# Connectors.net
KiCad netlist of a schematic drawn in Altium Designer
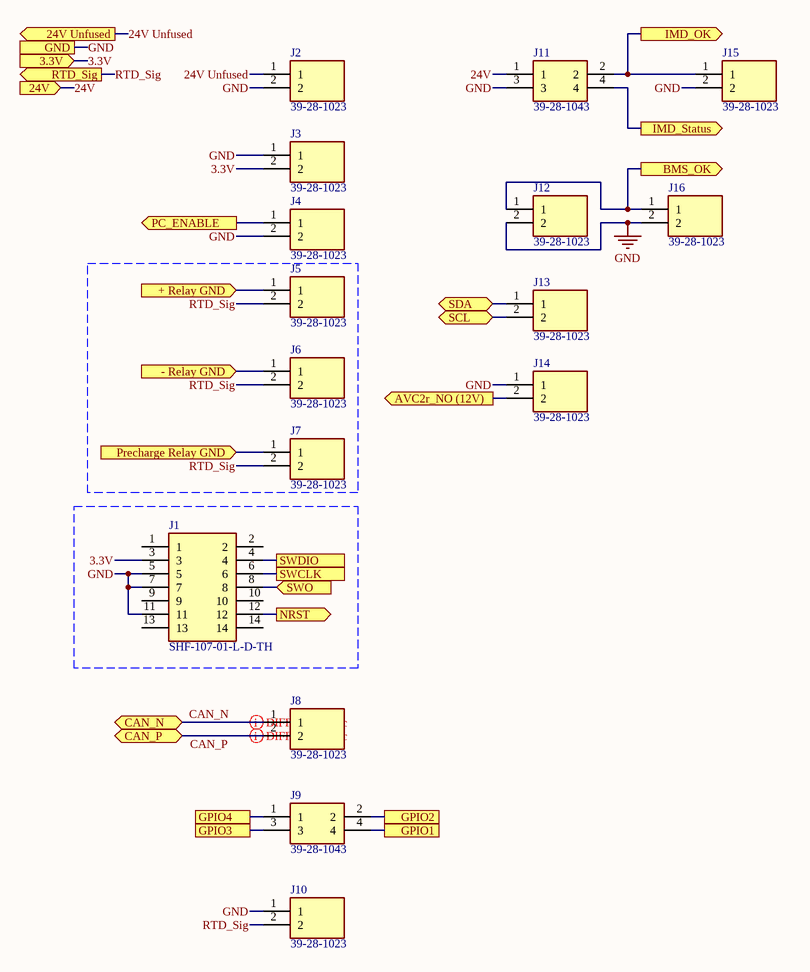
[diagram p0: Connectors.SchDoc]

(export (version "E")
  (design (tool "Eeschema 10.0.6"))
  (components
    (comp (ref "J1")
      (value "SHF-107-01-L-D-TH")
      (footprint "SamacSys:SHF10701LDTH")
      (description "Connector")
      (fields (field (name "MOUSER PART NUMBER") "200-SHF10701LDTH"))
      (libsource (lib "SamacSys") (part "SHF-107-01-L-D-TH"))
    )
    (comp (ref "J2")
      (value "39-28-1023")
      (footprint "SamacSys:39-28-1023")
      (description "Connector")
      (fields (field (name "MOUSER PART NUMBER") "538-39-28-1023"))
      (libsource (lib "SamacSys") (part "39-28-1023"))
    )
    (comp (ref "J3")
      (value "39-28-1023")
      (footprint "SamacSys:39-28-1023")
      (description "Connector")
      (fields (field (name "MOUSER PART NUMBER") "538-39-28-1023"))
      (libsource (lib "SamacSys") (part "39-28-1023"))
    )
    (comp (ref "J4")
      (value "39-28-1023")
      (footprint "SamacSys:39-28-1023")
      (description "Connector")
      (fields (field (name "MOUSER PART NUMBER") "538-39-28-1023"))
      (libsource (lib "SamacSys") (part "39-28-1023"))
    )
    (comp (ref "J5")
      (value "39-28-1023")
      (footprint "SamacSys:39-28-1023")
      (description "Connector")
      (fields (field (name "MOUSER PART NUMBER") "538-39-28-1023"))
      (libsource (lib "SamacSys") (part "39-28-1023"))
    )
    (comp (ref "J6")
      (value "39-28-1023")
      (footprint "SamacSys:39-28-1023")
      (description "Connector")
      (fields (field (name "MOUSER PART NUMBER") "538-39-28-1023"))
      (libsource (lib "SamacSys") (part "39-28-1023"))
    )
    (comp (ref "J7")
      (value "39-28-1023")
      (footprint "SamacSys:39-28-1023")
      (description "Connector")
      (fields (field (name "MOUSER PART NUMBER") "538-39-28-1023"))
      (libsource (lib "SamacSys") (part "39-28-1023"))
    )
    (comp (ref "J8")
      (value "39-28-1023")
      (footprint "SamacSys:39-28-1023")
      (description "Connector")
      (fields (field (name "MOUSER PART NUMBER") "538-39-28-1023"))
      (libsource (lib "SamacSys") (part "39-28-1023"))
    )
    (comp (ref "J9")
      (value "39-28-1043")
      (footprint "SamacSys:39-28-1043")
      (description "Connector")
      (fields (field (name "MOUSER PART NUMBER") "538-39-28-1043"))
      (libsource (lib "*") (part "39-28-1043"))
    )
    (comp (ref "J10")
      (value "39-28-1023")
      (footprint "SamacSys:39-28-1023")
      (description "Connector")
      (fields (field (name "MOUSER PART NUMBER") "538-39-28-1023"))
      (libsource (lib "SamacSys") (part "39-28-1023"))
    )
    (comp (ref "J11")
      (value "39-28-1043")
      (footprint "SamacSys:39-28-1043")
      (description "Connector")
      (fields (field (name "MOUSER PART NUMBER") "538-39-28-1043"))
      (libsource (lib "*") (part "39-28-1043"))
    )
    (comp (ref "J12")
      (value "39-28-1023")
      (footprint "SamacSys:39-28-1023")
      (description "Connector")
      (fields (field (name "MOUSER PART NUMBER") "538-39-28-1023"))
      (libsource (lib "SamacSys") (part "39-28-1023"))
    )
    (comp (ref "J13")
      (value "39-28-1023")
      (footprint "SamacSys:39-28-1023")
      (description "Connector")
      (fields (field (name "MOUSER PART NUMBER") "538-39-28-1023"))
      (libsource (lib "SamacSys") (part "39-28-1023"))
    )
    (comp (ref "J14")
      (value "39-28-1023")
      (footprint "SamacSys:39-28-1023")
      (description "Connector")
      (fields (field (name "MOUSER PART NUMBER") "538-39-28-1023"))
      (libsource (lib "SamacSys") (part "39-28-1023"))
    )
    (comp (ref "J15")
      (value "39-28-1023")
      (footprint "SamacSys:39-28-1023")
      (description "Connector")
      (fields (field (name "MOUSER PART NUMBER") "538-39-28-1023"))
      (libsource (lib "SamacSys") (part "39-28-1023"))
    )
    (comp (ref "J16")
      (value "39-28-1023")
      (footprint "SamacSys:39-28-1023")
      (description "Connector")
      (fields (field (name "MOUSER PART NUMBER") "538-39-28-1023"))
      (libsource (lib "SamacSys") (part "39-28-1023"))
    )
  )
  (nets
    (net (code "1") (name "/+ Relay GND") (class "Default")
      (node (ref "J5") (pin "1") (pinfunction "1_1") (pintype "passive"))
    )
    (net (code "2") (name "/- Relay GND") (class "Default")
      (node (ref "J6") (pin "1") (pinfunction "1_1") (pintype "passive"))
    )
    (net (code "3") (name "/3.3V") (class "Default")
      (node (ref "J1") (pin "3") (pinfunction "3_3") (pintype "passive"))
      (node (ref "J3") (pin "2") (pinfunction "2_2") (pintype "passive"))
    )
    (net (code "4") (name "/24V") (class "Default")
      (node (ref "J11") (pin "1") (pinfunction "1_1") (pintype "passive"))
    )
    (net (code "5") (name "/24V Unfused") (class "Default")
      (node (ref "J2") (pin "1") (pinfunction "1_1") (pintype "passive"))
    )
    (net (code "6") (name "/AVC2r_NO (12V)") (class "Default")
      (node (ref "J14") (pin "2") (pinfunction "2_2") (pintype "passive"))
    )
    (net (code "7") (name "/BMS_OK") (class "Default")
      (node (ref "J12") (pin "1") (pinfunction "1_1") (pintype "passive"))
      (node (ref "J16") (pin "1") (pinfunction "1_1") (pintype "passive"))
    )
    (net (code "8") (name "/CAN_N") (class "Default")
      (node (ref "J8") (pin "1") (pinfunction "1_1") (pintype "passive"))
    )
    (net (code "9") (name "/CAN_P") (class "Default")
      (node (ref "J8") (pin "2") (pinfunction "2_2") (pintype "passive"))
    )
    (net (code "10") (name "/GPIO1") (class "Default")
      (node (ref "J9") (pin "4") (pinfunction "4_4") (pintype "passive"))
    )
    (net (code "11") (name "/GPIO2") (class "Default")
      (node (ref "J9") (pin "2") (pinfunction "2_2") (pintype "passive"))
    )
    (net (code "12") (name "/GPIO3") (class "Default")
      (node (ref "J9") (pin "3") (pinfunction "3_3") (pintype "passive"))
    )
    (net (code "13") (name "/GPIO4") (class "Default")
      (node (ref "J9") (pin "1") (pinfunction "1_1") (pintype "passive"))
    )
    (net (code "14") (name "/IMD_OK") (class "Default")
      (node (ref "J11") (pin "2") (pinfunction "2_2") (pintype "passive"))
      (node (ref "J15") (pin "1") (pinfunction "1_1") (pintype "passive"))
    )
    (net (code "15") (name "/IMD_Status") (class "Default")
      (node (ref "J11") (pin "4") (pinfunction "4_4") (pintype "passive"))
    )
    (net (code "16") (name "/NRST") (class "Default")
      (node (ref "J1") (pin "12") (pinfunction "12_12") (pintype "passive"))
    )
    (net (code "17") (name "/PC_ENABLE") (class "Default")
      (node (ref "J4") (pin "1") (pinfunction "1_1") (pintype "passive"))
    )
    (net (code "18") (name "/Precharge Relay GND") (class "Default")
      (node (ref "J7") (pin "1") (pinfunction "1_1") (pintype "passive"))
    )
    (net (code "19") (name "/RTD_Sig") (class "Default")
      (node (ref "J10") (pin "2") (pinfunction "2_2") (pintype "passive"))
      (node (ref "J5") (pin "2") (pinfunction "2_2") (pintype "passive"))
      (node (ref "J6") (pin "2") (pinfunction "2_2") (pintype "passive"))
      (node (ref "J7") (pin "2") (pinfunction "2_2") (pintype "passive"))
    )
    (net (code "20") (name "/SCL") (class "Default")
      (node (ref "J13") (pin "2") (pinfunction "2_2") (pintype "passive"))
    )
    (net (code "21") (name "/SDA") (class "Default")
      (node (ref "J13") (pin "1") (pinfunction "1_1") (pintype "passive"))
    )
    (net (code "22") (name "/SWCLK") (class "Default")
      (node (ref "J1") (pin "6") (pinfunction "6_6") (pintype "passive"))
    )
    (net (code "23") (name "/SWDIO") (class "Default")
      (node (ref "J1") (pin "4") (pinfunction "4_4") (pintype "passive"))
    )
    (net (code "24") (name "/SWO") (class "Default")
      (node (ref "J1") (pin "8") (pinfunction "8_8") (pintype "passive"))
    )
    (net (code "25") (name "GND") (class "Default")
      (node (ref "J1") (pin "11") (pinfunction "11_11") (pintype "passive"))
      (node (ref "J1") (pin "5") (pinfunction "5_5") (pintype "passive"))
      (node (ref "J1") (pin "7") (pinfunction "7_7") (pintype "passive"))
      (node (ref "J10") (pin "1") (pinfunction "1_1") (pintype "passive"))
      (node (ref "J11") (pin "3") (pinfunction "3_3") (pintype "passive"))
      (node (ref "J12") (pin "2") (pinfunction "2_2") (pintype "passive"))
      (node (ref "J14") (pin "1") (pinfunction "1_1") (pintype "passive"))
      (node (ref "J15") (pin "2") (pinfunction "2_2") (pintype "passive"))
      (node (ref "J16") (pin "2") (pinfunction "2_2") (pintype "passive"))
      (node (ref "J2") (pin "2") (pinfunction "2_2") (pintype "passive"))
      (node (ref "J3") (pin "1") (pinfunction "1_1") (pintype "passive"))
      (node (ref "J4") (pin "2") (pinfunction "2_2") (pintype "passive"))
    )
    (net (code "26") (name "unconnected-(J1-Pad1)") (class "Default")
      (node (ref "J1") (pin "1") (pinfunction "1_1") (pintype "passive"))
    )
    (net (code "27") (name "unconnected-(J1-Pad2)") (class "Default")
      (node (ref "J1") (pin "2") (pinfunction "2_2") (pintype "passive"))
    )
    (net (code "28") (name "unconnected-(J1-Pad9)") (class "Default")
      (node (ref "J1") (pin "9") (pinfunction "9_9") (pintype "passive"))
    )
    (net (code "29") (name "unconnected-(J1-Pad10)") (class "Default")
      (node (ref "J1") (pin "10") (pinfunction "10_10") (pintype "passive"))
    )
    (net (code "30") (name "unconnected-(J1-Pad13)") (class "Default")
      (node (ref "J1") (pin "13") (pinfunction "13_13") (pintype "passive"))
    )
    (net (code "31") (name "unconnected-(J1-Pad14)") (class "Default")
      (node (ref "J1") (pin "14") (pinfunction "14_14") (pintype "passive"))
    )
  )
)
